# 08-NANDStatusLed.net
KiCad netlist of a schematic drawn in Altium Designer
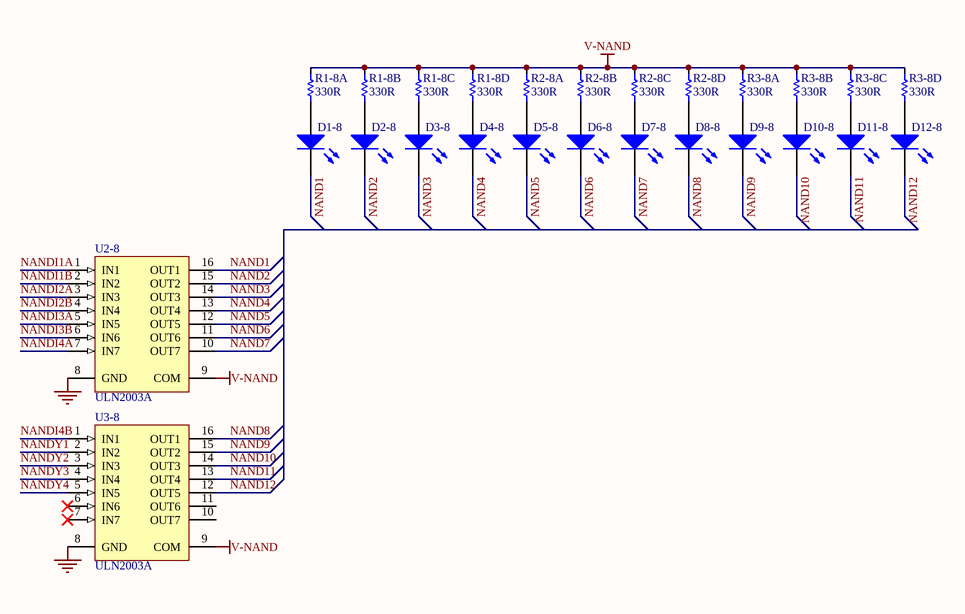
[diagram p0: 08-NANDStatusLed.SchDoc]

(export (version "E")
  (design (tool "Eeschema 10.0.6"))
  (components
    (comp (ref "D1-8")
      (value "LED")
      (footprint "LED-0805")
      (description "Typical RED, GREEN, YELLOW, AMBER GaAs LED")
      (fields (field (name "PUBLISHER") "Altium Limited"))
      (libsource (lib "Miscellaneous Devices") (part "LED2"))
    )
    (comp (ref "D2-8")
      (value "LED")
      (footprint "LED-0805")
      (description "Typical RED, GREEN, YELLOW, AMBER GaAs LED")
      (fields (field (name "PUBLISHER") "Altium Limited"))
      (libsource (lib "Miscellaneous Devices") (part "LED2"))
    )
    (comp (ref "D3-8")
      (value "LED")
      (footprint "LED-0805")
      (description "Typical RED, GREEN, YELLOW, AMBER GaAs LED")
      (fields (field (name "PUBLISHER") "Altium Limited"))
      (libsource (lib "Miscellaneous Devices") (part "LED2"))
    )
    (comp (ref "D4-8")
      (value "LED")
      (footprint "LED-0805")
      (description "Typical RED, GREEN, YELLOW, AMBER GaAs LED")
      (fields (field (name "PUBLISHER") "Altium Limited"))
      (libsource (lib "Miscellaneous Devices") (part "LED2"))
    )
    (comp (ref "D5-8")
      (value "LED")
      (footprint "LED-0805")
      (description "Typical RED, GREEN, YELLOW, AMBER GaAs LED")
      (fields (field (name "PUBLISHER") "Altium Limited"))
      (libsource (lib "Miscellaneous Devices") (part "LED2"))
    )
    (comp (ref "D6-8")
      (value "LED")
      (footprint "LED-0805")
      (description "Typical RED, GREEN, YELLOW, AMBER GaAs LED")
      (fields (field (name "PUBLISHER") "Altium Limited"))
      (libsource (lib "Miscellaneous Devices") (part "LED2"))
    )
    (comp (ref "D7-8")
      (value "LED")
      (footprint "LED-0805")
      (description "Typical RED, GREEN, YELLOW, AMBER GaAs LED")
      (fields (field (name "PUBLISHER") "Altium Limited"))
      (libsource (lib "Miscellaneous Devices") (part "LED2"))
    )
    (comp (ref "D8-8")
      (value "LED")
      (footprint "LED-0805")
      (description "Typical RED, GREEN, YELLOW, AMBER GaAs LED")
      (fields (field (name "PUBLISHER") "Altium Limited"))
      (libsource (lib "Miscellaneous Devices") (part "LED2"))
    )
    (comp (ref "D9-8")
      (value "LED")
      (footprint "LED-0805")
      (description "Typical RED, GREEN, YELLOW, AMBER GaAs LED")
      (fields (field (name "PUBLISHER") "Altium Limited"))
      (libsource (lib "Miscellaneous Devices") (part "LED2"))
    )
    (comp (ref "D10-8")
      (value "LED")
      (footprint "LED-0805")
      (description "Typical RED, GREEN, YELLOW, AMBER GaAs LED")
      (fields (field (name "PUBLISHER") "Altium Limited"))
      (libsource (lib "Miscellaneous Devices") (part "LED2"))
    )
    (comp (ref "D11-8")
      (value "LED")
      (footprint "LED-0805")
      (description "Typical RED, GREEN, YELLOW, AMBER GaAs LED")
      (fields (field (name "PUBLISHER") "Altium Limited"))
      (libsource (lib "Miscellaneous Devices") (part "LED2"))
    )
    (comp (ref "D12-8")
      (value "LED")
      (footprint "LED-0805")
      (description "Typical RED, GREEN, YELLOW, AMBER GaAs LED")
      (fields (field (name "PUBLISHER") "Altium Limited"))
      (libsource (lib "Miscellaneous Devices") (part "LED2"))
    )
    (comp (ref "R1-8")
      (value "330R")
      (footprint "R-Array-0603-4")
      (description "RES ARRAY 4 RES 330 OHM 1206")
      (fields
        (field (name "DIGI-KEY PART NUMBER") "Y9331TR-ND")
        (field (name "MANUFACTURER") "Panasonic Electronic Components")
      )
      (libsource (lib "Dlib") (part "Res Array 4"))
    )
    (comp (ref "R2-8")
      (value "330R")
      (footprint "R-Array-0603-4")
      (description "RES ARRAY 4 RES 330 OHM 1206")
      (fields
        (field (name "DIGI-KEY PART NUMBER") "Y9331TR-ND")
        (field (name "MANUFACTURER") "Panasonic Electronic Components")
      )
      (libsource (lib "Dlib") (part "Res Array 4"))
    )
    (comp (ref "R3-8")
      (value "330R")
      (footprint "R-Array-0603-4")
      (description "RES ARRAY 4 RES 330 OHM 1206")
      (fields
        (field (name "DIGI-KEY PART NUMBER") "Y9331TR-ND")
        (field (name "MANUFACTURER") "Panasonic Electronic Components")
      )
      (libsource (lib "Dlib") (part "Res Array 4"))
    )
    (comp (ref "U2-8")
      (value "ULN2003A")
      (footprint "SOIC-16")
      (description "High-Voltage, High-Current Darlington Array")
      (fields (field (name "PUBLISHER") "Altium Limited"))
      (libsource (lib "Allegro Interface Darlington Driver") (part "ULN2003A"))
    )
    (comp (ref "U3-8")
      (value "ULN2003A")
      (footprint "SOIC-16")
      (description "High-Voltage, High-Current Darlington Array")
      (fields (field (name "PUBLISHER") "Altium Limited"))
      (libsource (lib "Allegro Interface Darlington Driver") (part "ULN2003A"))
    )
  )
  (nets
    (net (code "1") (name "/NAND1") (class "Default")
      (node (ref "D1-8") (pin "2") (pinfunction "K_2") (pintype "passive"))
      (node (ref "U2-8") (pin "16") (pinfunction "OUT1_16") (pintype "open_collector"))
    )
    (net (code "2") (name "/NAND2") (class "Default")
      (node (ref "D2-8") (pin "2") (pinfunction "K_2") (pintype "passive"))
      (node (ref "U2-8") (pin "15") (pinfunction "OUT2_15") (pintype "open_collector"))
    )
    (net (code "3") (name "/NAND3") (class "Default")
      (node (ref "D3-8") (pin "2") (pinfunction "K_2") (pintype "passive"))
      (node (ref "U2-8") (pin "14") (pinfunction "OUT3_14") (pintype "open_collector"))
    )
    (net (code "4") (name "/NAND4") (class "Default")
      (node (ref "D4-8") (pin "2") (pinfunction "K_2") (pintype "passive"))
      (node (ref "U2-8") (pin "13") (pinfunction "OUT4_13") (pintype "open_collector"))
    )
    (net (code "5") (name "/NAND5") (class "Default")
      (node (ref "D5-8") (pin "2") (pinfunction "K_2") (pintype "passive"))
      (node (ref "U2-8") (pin "12") (pinfunction "OUT5_12") (pintype "open_collector"))
    )
    (net (code "6") (name "/NAND6") (class "Default")
      (node (ref "D6-8") (pin "2") (pinfunction "K_2") (pintype "passive"))
      (node (ref "U2-8") (pin "11") (pinfunction "OUT6_11") (pintype "open_collector"))
    )
    (net (code "7") (name "/NAND7") (class "Default")
      (node (ref "D7-8") (pin "2") (pinfunction "K_2") (pintype "passive"))
      (node (ref "U2-8") (pin "10") (pinfunction "OUT7_10") (pintype "open_collector"))
    )
    (net (code "8") (name "/NAND8") (class "Default")
      (node (ref "D8-8") (pin "2") (pinfunction "K_2") (pintype "passive"))
      (node (ref "U3-8") (pin "16") (pinfunction "OUT1_16") (pintype "open_collector"))
    )
    (net (code "9") (name "/NAND9") (class "Default")
      (node (ref "D9-8") (pin "2") (pinfunction "K_2") (pintype "passive"))
      (node (ref "U3-8") (pin "15") (pinfunction "OUT2_15") (pintype "open_collector"))
    )
    (net (code "10") (name "/NAND10") (class "Default")
      (node (ref "D10-8") (pin "2") (pinfunction "K_2") (pintype "passive"))
      (node (ref "U3-8") (pin "14") (pinfunction "OUT3_14") (pintype "open_collector"))
    )
    (net (code "11") (name "/NAND11") (class "Default")
      (node (ref "D11-8") (pin "2") (pinfunction "K_2") (pintype "passive"))
      (node (ref "U3-8") (pin "13") (pinfunction "OUT4_13") (pintype "open_collector"))
    )
    (net (code "12") (name "/NAND12") (class "Default")
      (node (ref "D12-8") (pin "2") (pinfunction "K_2") (pintype "passive"))
      (node (ref "U3-8") (pin "12") (pinfunction "OUT5_12") (pintype "open_collector"))
    )
    (net (code "13") (name "/NANDI1A") (class "Default")
      (node (ref "U2-8") (pin "1") (pinfunction "IN1_1") (pintype "input"))
    )
    (net (code "14") (name "/NANDI1B") (class "Default")
      (node (ref "U2-8") (pin "2") (pinfunction "IN2_2") (pintype "input"))
    )
    (net (code "15") (name "/NANDI2A") (class "Default")
      (node (ref "U2-8") (pin "3") (pinfunction "IN3_3") (pintype "input"))
    )
    (net (code "16") (name "/NANDI2B") (class "Default")
      (node (ref "U2-8") (pin "4") (pinfunction "IN4_4") (pintype "input"))
    )
    (net (code "17") (name "/NANDI3A") (class "Default")
      (node (ref "U2-8") (pin "5") (pinfunction "IN5_5") (pintype "input"))
    )
    (net (code "18") (name "/NANDI3B") (class "Default")
      (node (ref "U2-8") (pin "6") (pinfunction "IN6_6") (pintype "input"))
    )
    (net (code "19") (name "/NANDI4A") (class "Default")
      (node (ref "U2-8") (pin "7") (pinfunction "IN7_7") (pintype "input"))
    )
    (net (code "20") (name "/NANDI4B") (class "Default")
      (node (ref "U3-8") (pin "1") (pinfunction "IN1_1") (pintype "input"))
    )
    (net (code "21") (name "/NANDY1") (class "Default")
      (node (ref "U3-8") (pin "2") (pinfunction "IN2_2") (pintype "input"))
    )
    (net (code "22") (name "/NANDY2") (class "Default")
      (node (ref "U3-8") (pin "3") (pinfunction "IN3_3") (pintype "input"))
    )
    (net (code "23") (name "/NANDY3") (class "Default")
      (node (ref "U3-8") (pin "4") (pinfunction "IN4_4") (pintype "input"))
    )
    (net (code "24") (name "/NANDY4") (class "Default")
      (node (ref "U3-8") (pin "5") (pinfunction "IN5_5") (pintype "input"))
    )
    (net (code "25") (name "GND") (class "Default")
      (node (ref "U2-8") (pin "8") (pinfunction "GND_8") (pintype "power_in"))
      (node (ref "U3-8") (pin "8") (pinfunction "GND_8") (pintype "power_in"))
    )
    (net (code "26") (name "Net-(D1-8-A)") (class "Default")
      (node (ref "D1-8") (pin "1") (pinfunction "A_1") (pintype "passive"))
      (node (ref "R1-8") (pin "1") (pinfunction "1_1") (pintype "passive"))
    )
    (net (code "27") (name "Net-(D2-8-A)") (class "Default")
      (node (ref "D2-8") (pin "1") (pinfunction "A_1") (pintype "passive"))
      (node (ref "R1-8") (pin "3") (pinfunction "1_3") (pintype "passive"))
    )
    (net (code "28") (name "Net-(D3-8-A)") (class "Default")
      (node (ref "D3-8") (pin "1") (pinfunction "A_1") (pintype "passive"))
      (node (ref "R1-8") (pin "5") (pinfunction "1_5") (pintype "passive"))
    )
    (net (code "29") (name "Net-(D4-8-A)") (class "Default")
      (node (ref "D4-8") (pin "1") (pinfunction "A_1") (pintype "passive"))
      (node (ref "R1-8") (pin "7") (pinfunction "1_7") (pintype "passive"))
    )
    (net (code "30") (name "Net-(D5-8-A)") (class "Default")
      (node (ref "D5-8") (pin "1") (pinfunction "A_1") (pintype "passive"))
      (node (ref "R2-8") (pin "1") (pinfunction "1_1") (pintype "passive"))
    )
    (net (code "31") (name "Net-(D6-8-A)") (class "Default")
      (node (ref "D6-8") (pin "1") (pinfunction "A_1") (pintype "passive"))
      (node (ref "R2-8") (pin "3") (pinfunction "1_3") (pintype "passive"))
    )
    (net (code "32") (name "Net-(D7-8-A)") (class "Default")
      (node (ref "D7-8") (pin "1") (pinfunction "A_1") (pintype "passive"))
      (node (ref "R2-8") (pin "5") (pinfunction "1_5") (pintype "passive"))
    )
    (net (code "33") (name "Net-(D8-8-A)") (class "Default")
      (node (ref "D8-8") (pin "1") (pinfunction "A_1") (pintype "passive"))
      (node (ref "R2-8") (pin "7") (pinfunction "1_7") (pintype "passive"))
    )
    (net (code "34") (name "Net-(D9-8-A)") (class "Default")
      (node (ref "D9-8") (pin "1") (pinfunction "A_1") (pintype "passive"))
      (node (ref "R3-8") (pin "1") (pinfunction "1_1") (pintype "passive"))
    )
    (net (code "35") (name "Net-(D10-8-A)") (class "Default")
      (node (ref "D10-8") (pin "1") (pinfunction "A_1") (pintype "passive"))
      (node (ref "R3-8") (pin "3") (pinfunction "1_3") (pintype "passive"))
    )
    (net (code "36") (name "Net-(D11-8-A)") (class "Default")
      (node (ref "D11-8") (pin "1") (pinfunction "A_1") (pintype "passive"))
      (node (ref "R3-8") (pin "5") (pinfunction "1_5") (pintype "passive"))
    )
    (net (code "37") (name "Net-(D12-8-A)") (class "Default")
      (node (ref "D12-8") (pin "1") (pinfunction "A_1") (pintype "passive"))
      (node (ref "R3-8") (pin "7") (pinfunction "1_7") (pintype "passive"))
    )
    (net (code "38") (name "V-NAND") (class "Default")
      (node (ref "R1-8") (pin "2") (pinfunction "2_2") (pintype "passive"))
      (node (ref "R1-8") (pin "4") (pinfunction "2_4") (pintype "passive"))
      (node (ref "R1-8") (pin "6") (pinfunction "2_6") (pintype "passive"))
      (node (ref "R1-8") (pin "8") (pinfunction "2_8") (pintype "passive"))
      (node (ref "R2-8") (pin "2") (pinfunction "2_2") (pintype "passive"))
      (node (ref "R2-8") (pin "4") (pinfunction "2_4") (pintype "passive"))
      (node (ref "R2-8") (pin "6") (pinfunction "2_6") (pintype "passive"))
      (node (ref "R2-8") (pin "8") (pinfunction "2_8") (pintype "passive"))
      (node (ref "R3-8") (pin "2") (pinfunction "2_2") (pintype "passive"))
      (node (ref "R3-8") (pin "4") (pinfunction "2_4") (pintype "passive"))
      (node (ref "R3-8") (pin "6") (pinfunction "2_6") (pintype "passive"))
      (node (ref "R3-8") (pin "8") (pinfunction "2_8") (pintype "passive"))
      (node (ref "U2-8") (pin "9") (pinfunction "COM_9") (pintype "passive"))
      (node (ref "U3-8") (pin "9") (pinfunction "COM_9") (pintype "passive"))
    )
    (net (code "39") (name "unconnected-(U3-8-IN6-Pad6)") (class "Default")
      (node (ref "U3-8") (pin "6") (pinfunction "IN6_6") (pintype "input+no_connect"))
    )
    (net (code "40") (name "unconnected-(U3-8-IN7-Pad7)") (class "Default")
      (node (ref "U3-8") (pin "7") (pinfunction "IN7_7") (pintype "input+no_connect"))
    )
    (net (code "41") (name "unconnected-(U3-8-OUT6-Pad11)") (class "Default")
      (node (ref "U3-8") (pin "11") (pinfunction "OUT6_11") (pintype "open_collector"))
    )
    (net (code "42") (name "unconnected-(U3-8-OUT7-Pad10)") (class "Default")
      (node (ref "U3-8") (pin "10") (pinfunction "OUT7_10") (pintype "open_collector"))
    )
  )
)
